# smartstand-clock-source-rev-a.net
KiCad netlist of a schematic drawn in EAGLE
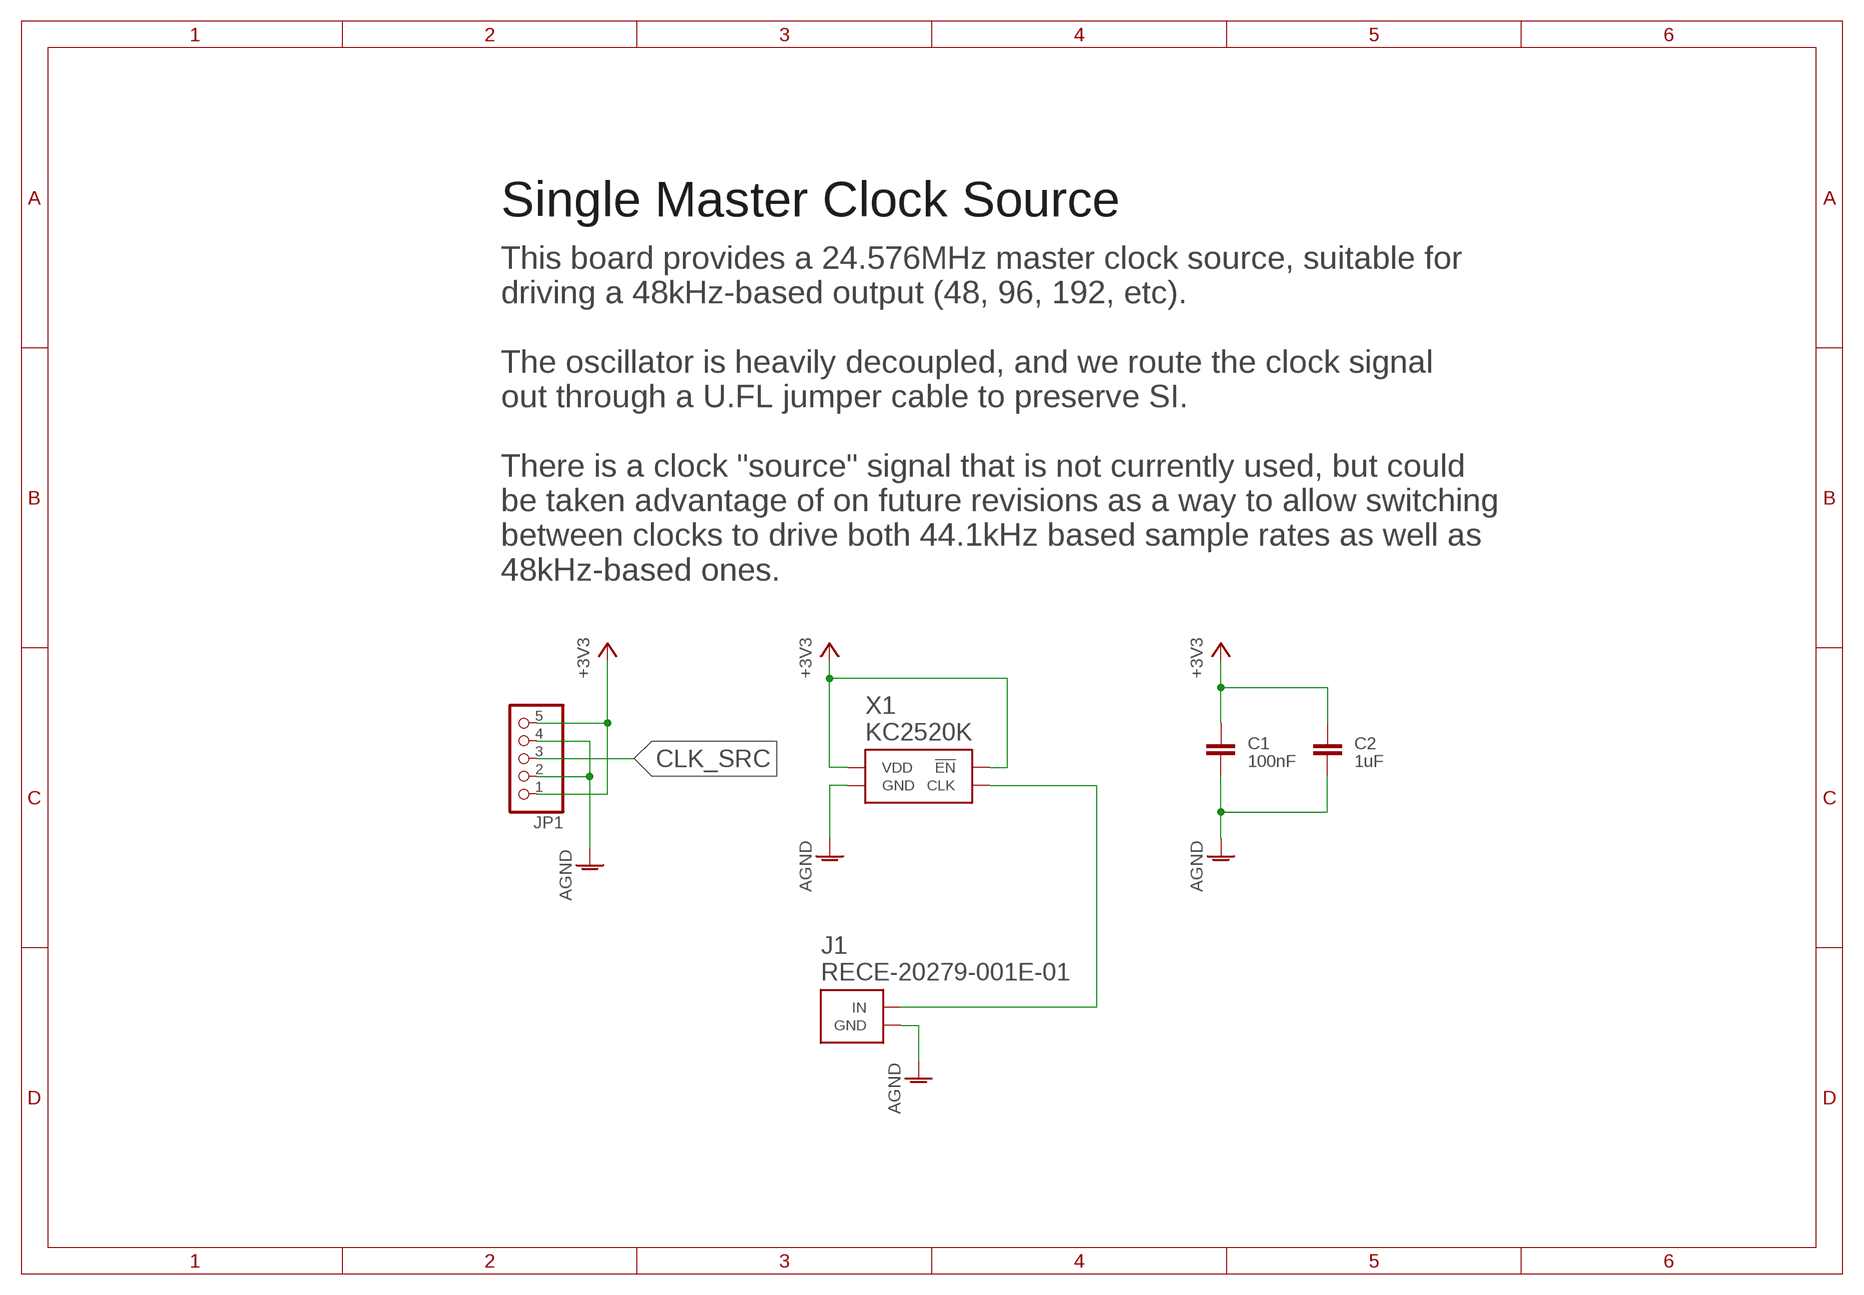
[diagram p0: schematic, sheet 1]

(export (version "E")
  (design (tool "Eeschema 10.0.6"))
  (components
    (comp (ref "C1")
      (value "100nF")
      (footprint "eagle-import:C0402")
      (libsource (lib "eagle-import") (part "C-EUC0402"))
    )
    (comp (ref "C2")
      (value "1uF")
      (footprint "eagle-import:C0603")
      (libsource (lib "eagle-import") (part "C-EUC0603"))
    )
    (comp (ref "J1")
      (value "RECE-20279-001E-01")
      (footprint "eagle-import:IPEX-MHF")
      (libsource (lib "eagle-import") (part "RECE-20279-001E-01"))
    )
    (comp (ref "JP1")
      (value "PINHD-1X5")
      (footprint "eagle-import:1X05")
      (libsource (lib "eagle-import") (part "PINHD-1X5"))
    )
    (comp (ref "X1")
      (value "KC2520K")
      (footprint "eagle-import:KC2520C")
      (libsource (lib "eagle-import") (part "KC2520K"))
    )
  )
  (nets
    (net (code "1") (name "+3V3") (class "Default")
      (node (ref "C1") (pin "1") (pinfunction "1_1") (pintype "passive"))
      (node (ref "C2") (pin "1") (pinfunction "1_1") (pintype "passive"))
      (node (ref "JP1") (pin "1") (pinfunction "1_1") (pintype "passive"))
      (node (ref "JP1") (pin "5") (pinfunction "5_5") (pintype "passive"))
      (node (ref "X1") (pin "P$1") (pinfunction "~{EN}_P$1") (pintype "bidirectional"))
      (node (ref "X1") (pin "P$4") (pinfunction "VDD_P$4") (pintype "bidirectional"))
    )
    (net (code "2") (name "AGND") (class "Default")
      (node (ref "C1") (pin "2") (pinfunction "2_2") (pintype "passive"))
      (node (ref "C2") (pin "2") (pinfunction "2_2") (pintype "passive"))
      (node (ref "J1") (pin "P$1") (pinfunction "GND_P$1") (pintype "bidirectional"))
      (node (ref "J1") (pin "P$2") (pinfunction "GND_P$2") (pintype "bidirectional"))
      (node (ref "JP1") (pin "2") (pinfunction "2_2") (pintype "passive"))
      (node (ref "JP1") (pin "4") (pinfunction "4_4") (pintype "passive"))
      (node (ref "X1") (pin "P$2") (pinfunction "GND_P$2") (pintype "bidirectional"))
    )
    (net (code "3") (name "CLK_SRC") (class "Default")
      (node (ref "JP1") (pin "3") (pinfunction "3_3") (pintype "passive"))
    )
    (net (code "4") (name "Net-(J1-IN)") (class "Default")
      (node (ref "J1") (pin "P$3") (pinfunction "IN_P$3") (pintype "bidirectional"))
      (node (ref "X1") (pin "P$3") (pinfunction "CLK_P$3") (pintype "bidirectional"))
    )
  )
)
